# MB_RELAY.net
KiCad netlist of a schematic drawn in Altium Designer
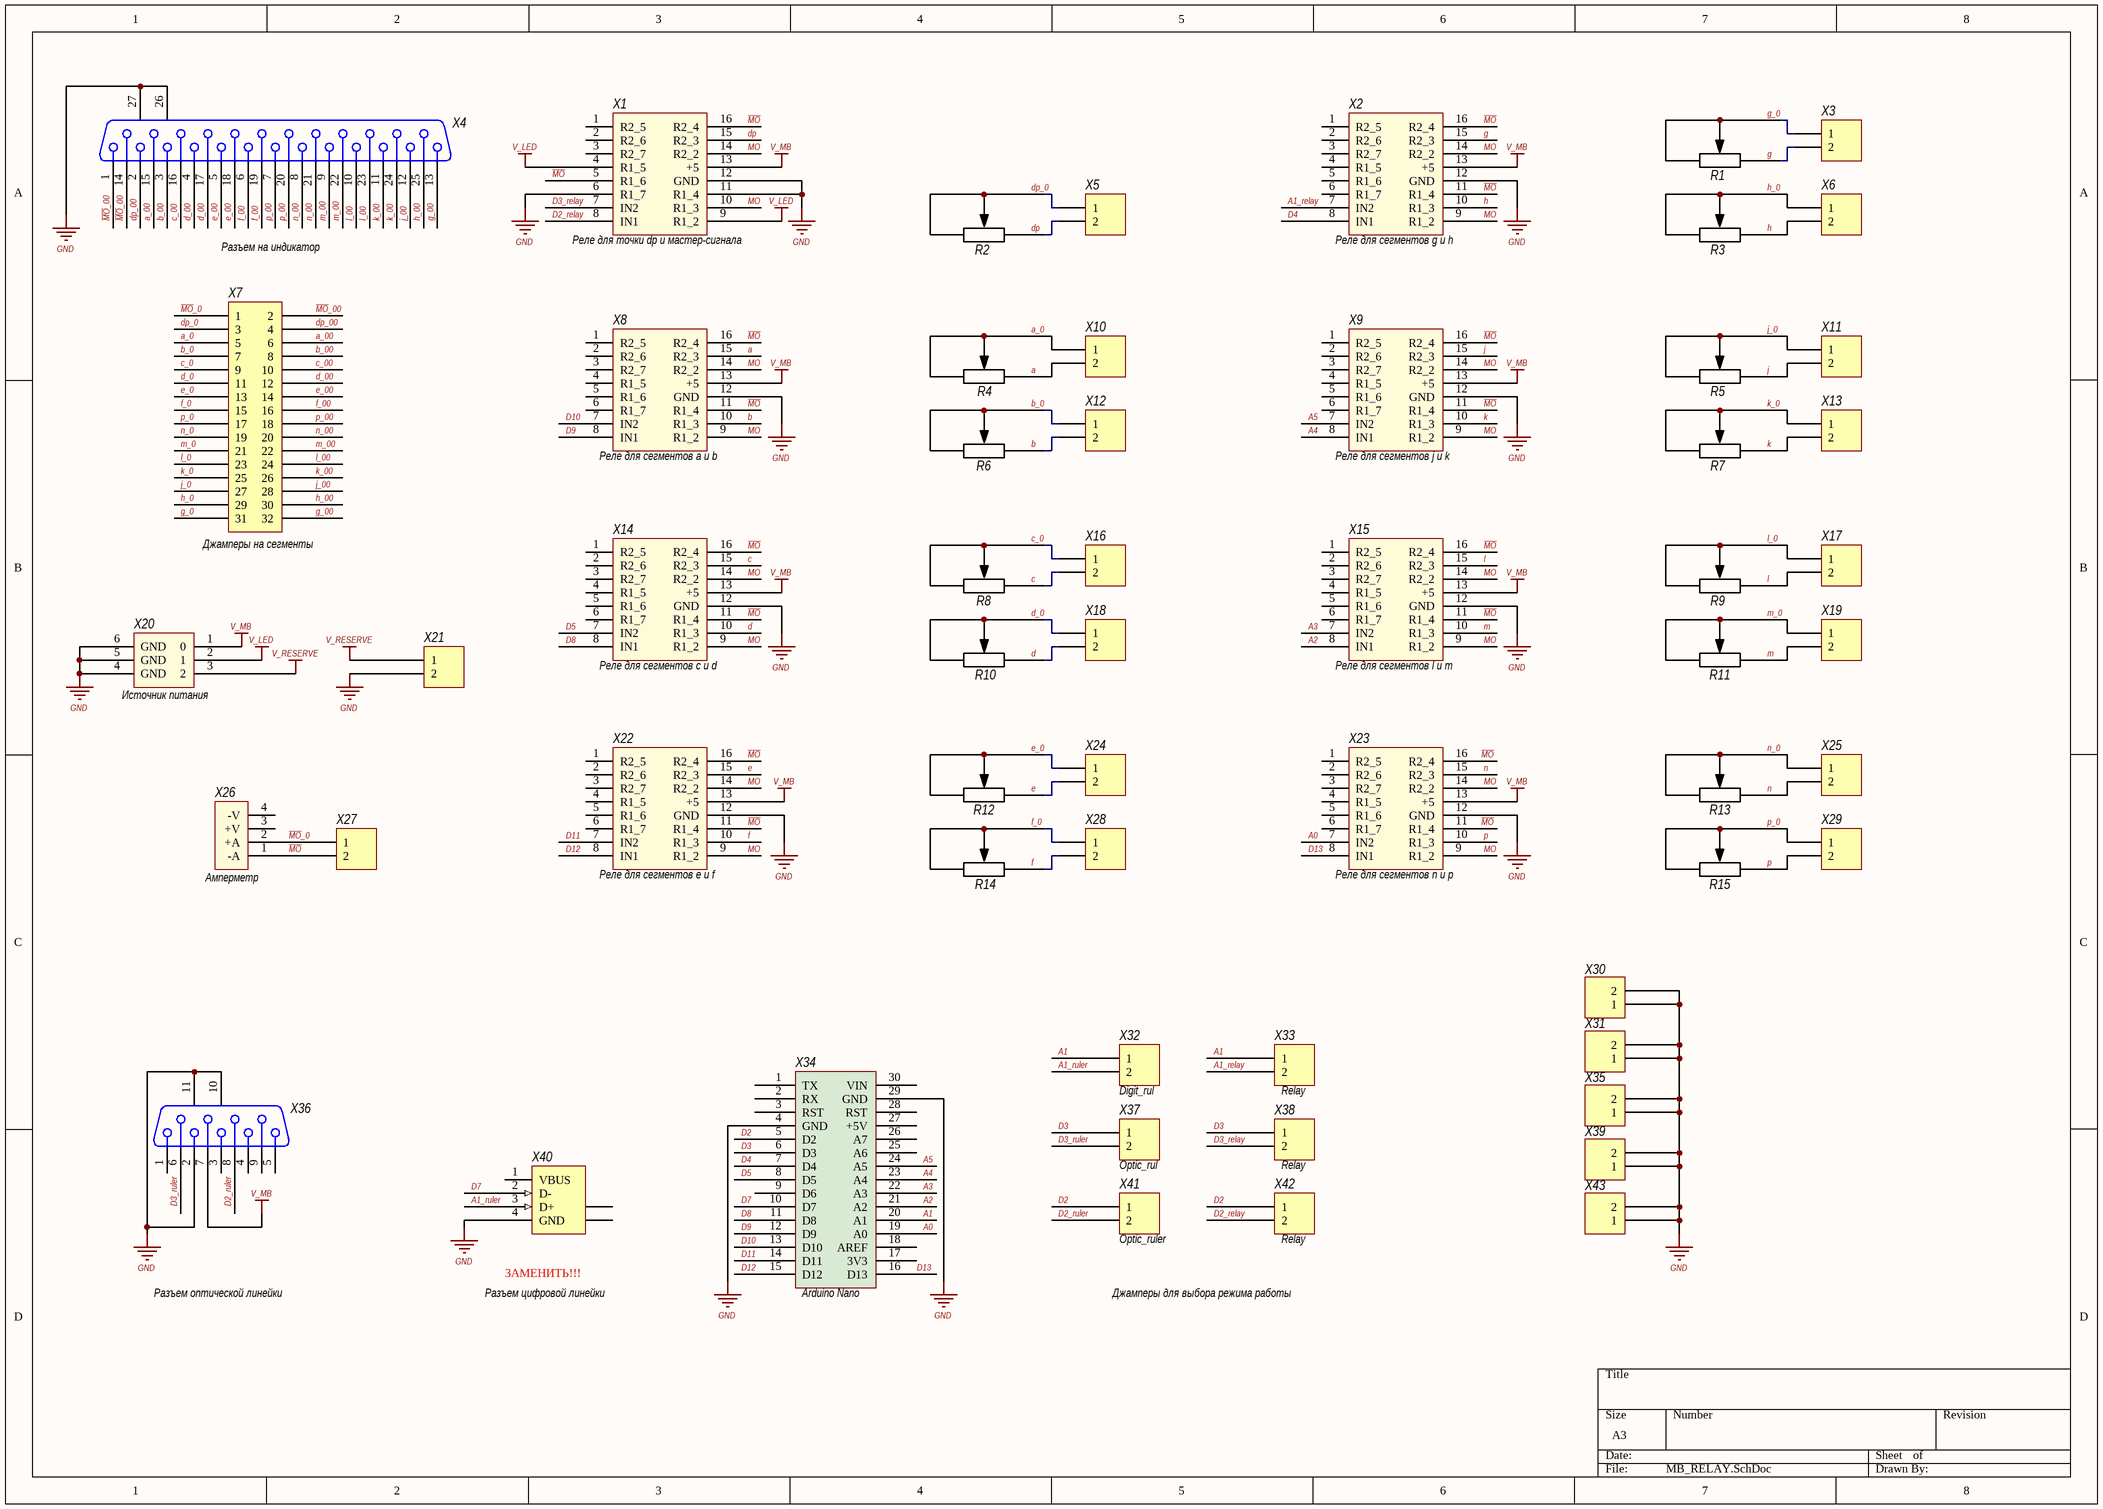
[diagram p0: MB_RELAY.SchDoc]

(export (version "E")
  (design (tool "Eeschema 10.0.6"))
  (components
    (comp (ref "R1")
      (value "RES 3266W")
      (footprint "aab_Passive:RES 3266W")
      (libsource (lib "aab_Schlib") (part "RES 3266W"))
    )
    (comp (ref "R2")
      (value "RES 3266W")
      (footprint "aab_Passive:RES 3266W")
      (libsource (lib "aab_Schlib") (part "RES 3266W"))
    )
    (comp (ref "R3")
      (value "RES 3266W")
      (footprint "aab_Passive:RES 3266W")
      (libsource (lib "aab_Schlib") (part "RES 3266W"))
    )
    (comp (ref "R4")
      (value "Переменнный резистор для")
      (footprint "aab_Passive:RES 3266W")
      (libsource (lib "aab_Schlib") (part "RES 3266W"))
    )
    (comp (ref "R5")
      (value "RES 3266W")
      (footprint "aab_Passive:RES 3266W")
      (libsource (lib "aab_Schlib") (part "RES 3266W"))
    )
    (comp (ref "R6")
      (value "RES 3266W")
      (footprint "aab_Passive:RES 3266W")
      (libsource (lib "aab_Schlib") (part "RES 3266W"))
    )
    (comp (ref "R7")
      (value "RES 3266W")
      (footprint "aab_Passive:RES 3266W")
      (libsource (lib "aab_Schlib") (part "RES 3266W"))
    )
    (comp (ref "R8")
      (value "RES 3266W")
      (footprint "aab_Passive:RES 3266W")
      (libsource (lib "aab_Schlib") (part "RES 3266W"))
    )
    (comp (ref "R9")
      (value "RES 3266W")
      (footprint "aab_Passive:RES 3266W")
      (libsource (lib "aab_Schlib") (part "RES 3266W"))
    )
    (comp (ref "R10")
      (value "RES 3266W")
      (footprint "aab_Passive:RES 3266W")
      (libsource (lib "aab_Schlib") (part "RES 3266W"))
    )
    (comp (ref "R11")
      (value "RES 3266W")
      (footprint "aab_Passive:RES 3266W")
      (libsource (lib "aab_Schlib") (part "RES 3266W"))
    )
    (comp (ref "R12")
      (value "RES 3266W")
      (footprint "aab_Passive:RES 3266W")
      (libsource (lib "aab_Schlib") (part "RES 3266W"))
    )
    (comp (ref "R13")
      (value "RES 3266W")
      (footprint "aab_Passive:RES 3266W")
      (libsource (lib "aab_Schlib") (part "RES 3266W"))
    )
    (comp (ref "R14")
      (value "RES 3266W")
      (footprint "aab_Passive:RES 3266W")
      (libsource (lib "aab_Schlib") (part "RES 3266W"))
    )
    (comp (ref "R15")
      (value "RES 3266W")
      (footprint "aab_Passive:RES 3266W")
      (libsource (lib "aab_Schlib") (part "RES 3266W"))
    )
    (comp (ref "X1")
      (value "Реле для точки dp и мастер-сигнала")
      (footprint "MEZ_RELAY")
      (libsource (lib "msp_SchLib") (part "MEZ_RELAY"))
    )
    (comp (ref "X2")
      (value "Реле для сегментов g и h")
      (footprint "MEZ_RELAY")
      (libsource (lib "msp_SchLib") (part "MEZ_RELAY"))
    )
    (comp (ref "X3")
      (value "GND")
      (footprint "HDR1X2")
      (description "Header, 2-Pin")
      (fields (field (name "PUBLISHER") "Altium Limited"))
      (libsource (lib "Miscellaneous Connectors") (part "Header 2"))
    )
    (comp (ref "X4")
      (value "D Connector 25")
      (footprint "DSUB1.385-2H25A")
      (description "Receptacle Assembly, 25 Position, Right Angle")
      (fields (field (name "PUBLISHER") "Altium Limited"))
      (libsource (lib "Miscellaneous Connectors") (part "D Connector 25"))
    )
    (comp (ref "X5")
      (value "GND")
      (footprint "HDR1X2")
      (description "Header, 2-Pin")
      (fields (field (name "PUBLISHER") "Altium Limited"))
      (libsource (lib "Miscellaneous Connectors") (part "Header 2"))
    )
    (comp (ref "X6")
      (value "GND")
      (footprint "HDR1X2")
      (description "Header, 2-Pin")
      (fields (field (name "PUBLISHER") "Altium Limited"))
      (libsource (lib "Miscellaneous Connectors") (part "Header 2"))
    )
    (comp (ref "X7")
      (value "Header 16X2")
      (footprint "HDR2X16")
      (description "Header, 16-Pin, Dual row")
      (fields (field (name "PUBLISHER") "Altium Limited"))
      (libsource (lib "Miscellaneous Connectors") (part "Header 16X2"))
    )
    (comp (ref "X8")
      (value "Реле для сегментов a и b")
      (footprint "MEZ_RELAY")
      (libsource (lib "msp_SchLib") (part "MEZ_RELAY"))
    )
    (comp (ref "X9")
      (value "Реле для сегментов j и k")
      (footprint "MEZ_RELAY")
      (libsource (lib "msp_SchLib") (part "MEZ_RELAY"))
    )
    (comp (ref "X10")
      (value "Header 2")
      (footprint "HDR1X2")
      (description "Header, 2-Pin")
      (fields (field (name "PUBLISHER") "Altium Limited"))
      (libsource (lib "Miscellaneous Connectors") (part "Header 2"))
    )
    (comp (ref "X11")
      (value "Header 2")
      (footprint "HDR1X2")
      (description "Header, 2-Pin")
      (fields (field (name "PUBLISHER") "Altium Limited"))
      (libsource (lib "Miscellaneous Connectors") (part "Header 2"))
    )
    (comp (ref "X12")
      (value "Header 2")
      (footprint "HDR1X2")
      (description "Header, 2-Pin")
      (fields (field (name "PUBLISHER") "Altium Limited"))
      (libsource (lib "Miscellaneous Connectors") (part "Header 2"))
    )
    (comp (ref "X13")
      (value "Header 2")
      (footprint "HDR1X2")
      (description "Header, 2-Pin")
      (fields (field (name "PUBLISHER") "Altium Limited"))
      (libsource (lib "Miscellaneous Connectors") (part "Header 2"))
    )
    (comp (ref "X14")
      (value "Реле для сегментов c и d")
      (footprint "MEZ_RELAY")
      (libsource (lib "msp_SchLib") (part "MEZ_RELAY"))
    )
    (comp (ref "X15")
      (value "Реле для сегментов l и m")
      (footprint "MEZ_RELAY")
      (libsource (lib "msp_SchLib") (part "MEZ_RELAY"))
    )
    (comp (ref "X16")
      (value "Header 2")
      (footprint "HDR1X2")
      (description "Header, 2-Pin")
      (fields (field (name "PUBLISHER") "Altium Limited"))
      (libsource (lib "Miscellaneous Connectors") (part "Header 2"))
    )
    (comp (ref "X17")
      (value "GND")
      (footprint "HDR1X2")
      (description "Header, 2-Pin")
      (fields (field (name "PUBLISHER") "Altium Limited"))
      (libsource (lib "Miscellaneous Connectors") (part "Header 2"))
    )
    (comp (ref "X18")
      (value "Header 2")
      (footprint "HDR1X2")
      (description "Header, 2-Pin")
      (fields (field (name "PUBLISHER") "Altium Limited"))
      (libsource (lib "Miscellaneous Connectors") (part "Header 2"))
    )
    (comp (ref "X19")
      (value "GND")
      (footprint "HDR1X2")
      (description "Header, 2-Pin")
      (fields (field (name "PUBLISHER") "Altium Limited"))
      (libsource (lib "Miscellaneous Connectors") (part "Header 2"))
    )
    (comp (ref "X20")
      (value "Источник питания")
      (footprint "vpl_Passive:POWER")
      (libsource (lib "msp_SchLib") (part "POWER"))
    )
    (comp (ref "X21")
      (value "Header 2")
      (footprint "HDR1X2")
      (description "Header, 2-Pin")
      (fields (field (name "PUBLISHER") "Altium Limited"))
      (libsource (lib "Miscellaneous Connectors") (part "Header 2"))
    )
    (comp (ref "X22")
      (value "Реле для сегментов e и f")
      (footprint "MEZ_RELAY")
      (libsource (lib "msp_SchLib") (part "MEZ_RELAY"))
    )
    (comp (ref "X23")
      (value "Реле для сегментов n и p")
      (footprint "MEZ_RELAY")
      (libsource (lib "msp_SchLib") (part "MEZ_RELAY"))
    )
    (comp (ref "X24")
      (value "GND")
      (footprint "HDR1X2")
      (description "Header, 2-Pin")
      (fields (field (name "PUBLISHER") "Altium Limited"))
      (libsource (lib "Miscellaneous Connectors") (part "Header 2"))
    )
    (comp (ref "X25")
      (value "GND")
      (footprint "HDR1X2")
      (description "Header, 2-Pin")
      (fields (field (name "PUBLISHER") "Altium Limited"))
      (libsource (lib "Miscellaneous Connectors") (part "Header 2"))
    )
    (comp (ref "X26")
      (value "Амперметр")
      (footprint "vpl_Passive:AMP_VOLTMETER")
      (libsource (lib "msp_SchLib") (part "AMP_VOLTMETR"))
    )
    (comp (ref "X27")
      (value "Header 2")
      (footprint "HDR1X2")
      (description "Header, 2-Pin")
      (fields (field (name "PUBLISHER") "Altium Limited"))
      (libsource (lib "Miscellaneous Connectors") (part "Header 2"))
    )
    (comp (ref "X28")
      (value "GND")
      (footprint "HDR1X2")
      (description "Header, 2-Pin")
      (fields (field (name "PUBLISHER") "Altium Limited"))
      (libsource (lib "Miscellaneous Connectors") (part "Header 2"))
    )
    (comp (ref "X29")
      (value "GND")
      (footprint "HDR1X2")
      (description "Header, 2-Pin")
      (fields (field (name "PUBLISHER") "Altium Limited"))
      (libsource (lib "Miscellaneous Connectors") (part "Header 2"))
    )
    (comp (ref "X30")
      (value "Header 2")
      (footprint "HDR1X2")
      (description "Header, 2-Pin")
      (fields (field (name "PUBLISHER") "Altium Limited"))
      (libsource (lib "") (part "Header 2_1"))
    )
    (comp (ref "X31")
      (value "GND")
      (footprint "HDR1X2")
      (description "Header, 2-Pin")
      (fields (field (name "PUBLISHER") "Altium Limited"))
      (libsource (lib "") (part "Header 2_1"))
    )
    (comp (ref "X32")
      (value "Digit_rul")
      (footprint "HDR1X2")
      (description "Header, 2-Pin")
      (fields (field (name "PUBLISHER") "Altium Limited"))
      (libsource (lib "Miscellaneous Connectors") (part "Header 2"))
    )
    (comp (ref "X33")
      (value "Relay")
      (footprint "HDR1X2")
      (description "Header, 2-Pin")
      (fields (field (name "PUBLISHER") "Altium Limited"))
      (libsource (lib "Miscellaneous Connectors") (part "Header 2"))
    )
    (comp (ref "X34")
      (value "Arduino Nano")
      (footprint "PCBComponent_1")
      (libsource (lib "Nano") (part "Component_1"))
    )
    (comp (ref "X35")
      (value "GND")
      (footprint "HDR1X2")
      (description "Header, 2-Pin")
      (fields (field (name "PUBLISHER") "Altium Limited"))
      (libsource (lib "") (part "Header 2_1"))
    )
    (comp (ref "X36")
      (value "D Connector 9")
      (footprint "DSUB1.385-2H9")
      (description "Receptacle Assembly, 9 Position, Right Angle")
      (fields (field (name "PUBLISHER") "Altium Limited"))
      (libsource (lib "Miscellaneous Connectors") (part "D Connector 9"))
    )
    (comp (ref "X37")
      (value "Optic_rul")
      (footprint "HDR1X2")
      (description "Header, 2-Pin")
      (fields (field (name "PUBLISHER") "Altium Limited"))
      (libsource (lib "Miscellaneous Connectors") (part "Header 2"))
    )
    (comp (ref "X38")
      (value "Relay")
      (footprint "HDR1X2")
      (description "Header, 2-Pin")
      (fields (field (name "PUBLISHER") "Altium Limited"))
      (libsource (lib "Miscellaneous Connectors") (part "Header 2"))
    )
    (comp (ref "X39")
      (value "GND")
      (footprint "HDR1X2")
      (description "Header, 2-Pin")
      (fields (field (name "PUBLISHER") "Altium Limited"))
      (libsource (lib "") (part "Header 2_1"))
    )
    (comp (ref "X40")
      (value "1-353576-1")
      (footprint "353576")
      (description "USB 1.1, Right Angle, SMT, A Type, Receptacle, 4 Position, White")
      (fields (field (name "PUBLISHER") "Altium Limited"))
      (libsource (lib "AMP Serial Bus USB") (part "1-353576-1"))
    )
    (comp (ref "X41")
      (value "Optic_ruler")
      (footprint "HDR1X2")
      (description "Header, 2-Pin")
      (fields (field (name "PUBLISHER") "Altium Limited"))
      (libsource (lib "Miscellaneous Connectors") (part "Header 2"))
    )
    (comp (ref "X42")
      (value "Relay")
      (footprint "HDR1X2")
      (description "Header, 2-Pin")
      (fields (field (name "PUBLISHER") "Altium Limited"))
      (libsource (lib "Miscellaneous Connectors") (part "Header 2"))
    )
    (comp (ref "X43")
      (value "GND")
      (footprint "HDR1X2")
      (description "Header, 2-Pin")
      (fields (field (name "PUBLISHER") "Altium Limited"))
      (libsource (lib "") (part "Header 2_1"))
    )
  )
  (nets
    (net (code "1") (name "/A0") (class "Default")
      (node (ref "X23") (pin "7") (pinfunction "IN2_7") (pintype "passive"))
      (node (ref "X34") (pin "19") (pinfunction "A0_19") (pintype "passive"))
    )
    (net (code "2") (name "/A1") (class "Default")
      (node (ref "X32") (pin "1") (pinfunction "1_1") (pintype "passive"))
      (node (ref "X33") (pin "1") (pinfunction "1_1") (pintype "passive"))
      (node (ref "X34") (pin "20") (pinfunction "A1_20") (pintype "passive"))
    )
    (net (code "3") (name "/A1_relay") (class "Default")
      (node (ref "X2") (pin "7") (pinfunction "IN2_7") (pintype "passive"))
      (node (ref "X33") (pin "2") (pinfunction "2_2") (pintype "passive"))
    )
    (net (code "4") (name "/A1_ruler") (class "Default")
      (node (ref "X32") (pin "2") (pinfunction "2_2") (pintype "passive"))
      (node (ref "X40") (pin "3") (pinfunction "D+_3") (pintype "input"))
    )
    (net (code "5") (name "/A2") (class "Default")
      (node (ref "X15") (pin "8") (pinfunction "IN1_8") (pintype "passive"))
      (node (ref "X34") (pin "21") (pinfunction "A2_21") (pintype "passive"))
    )
    (net (code "6") (name "/A3") (class "Default")
      (node (ref "X15") (pin "7") (pinfunction "IN2_7") (pintype "passive"))
      (node (ref "X34") (pin "22") (pinfunction "A3_22") (pintype "passive"))
    )
    (net (code "7") (name "/A4") (class "Default")
      (node (ref "X34") (pin "23") (pinfunction "A4_23") (pintype "passive"))
      (node (ref "X9") (pin "8") (pinfunction "IN1_8") (pintype "passive"))
    )
    (net (code "8") (name "/A5") (class "Default")
      (node (ref "X34") (pin "24") (pinfunction "A5_24") (pintype "passive"))
      (node (ref "X9") (pin "7") (pinfunction "IN2_7") (pintype "passive"))
    )
    (net (code "9") (name "/D2") (class "Default")
      (node (ref "X34") (pin "5") (pinfunction "D2_5") (pintype "passive"))
      (node (ref "X41") (pin "1") (pinfunction "1_1") (pintype "passive"))
      (node (ref "X42") (pin "1") (pinfunction "1_1") (pintype "passive"))
    )
    (net (code "10") (name "/D2_relay") (class "Default")
      (node (ref "X1") (pin "8") (pinfunction "IN1_8") (pintype "passive"))
      (node (ref "X42") (pin "2") (pinfunction "2_2") (pintype "passive"))
    )
    (net (code "11") (name "/D2_ruler") (class "Default")
      (node (ref "X36") (pin "8") (pinfunction "8_8") (pintype "passive"))
      (node (ref "X41") (pin "2") (pinfunction "2_2") (pintype "passive"))
    )
    (net (code "12") (name "/D3") (class "Default")
      (node (ref "X34") (pin "6") (pinfunction "D3_6") (pintype "passive"))
      (node (ref "X37") (pin "1") (pinfunction "1_1") (pintype "passive"))
      (node (ref "X38") (pin "1") (pinfunction "1_1") (pintype "passive"))
    )
    (net (code "13") (name "/D3_relay") (class "Default")
      (node (ref "X1") (pin "7") (pinfunction "IN2_7") (pintype "passive"))
      (node (ref "X38") (pin "2") (pinfunction "2_2") (pintype "passive"))
    )
    (net (code "14") (name "/D3_ruler") (class "Default")
      (node (ref "X36") (pin "6") (pinfunction "6_6") (pintype "passive"))
      (node (ref "X37") (pin "2") (pinfunction "2_2") (pintype "passive"))
    )
    (net (code "15") (name "/D4") (class "Default")
      (node (ref "X2") (pin "8") (pinfunction "IN1_8") (pintype "passive"))
      (node (ref "X34") (pin "7") (pinfunction "D4_7") (pintype "passive"))
    )
    (net (code "16") (name "/D5") (class "Default")
      (node (ref "X14") (pin "7") (pinfunction "IN2_7") (pintype "passive"))
      (node (ref "X34") (pin "8") (pinfunction "D5_8") (pintype "passive"))
    )
    (net (code "17") (name "/D7") (class "Default")
      (node (ref "X34") (pin "10") (pinfunction "D7_10") (pintype "passive"))
      (node (ref "X40") (pin "2") (pinfunction "D-_2") (pintype "input"))
    )
    (net (code "18") (name "/D8") (class "Default")
      (node (ref "X14") (pin "8") (pinfunction "IN1_8") (pintype "passive"))
      (node (ref "X34") (pin "11") (pinfunction "D8_11") (pintype "passive"))
    )
    (net (code "19") (name "/D9") (class "Default")
      (node (ref "X34") (pin "12") (pinfunction "D9_12") (pintype "passive"))
      (node (ref "X8") (pin "8") (pinfunction "IN1_8") (pintype "passive"))
    )
    (net (code "20") (name "/D10") (class "Default")
      (node (ref "X34") (pin "13") (pinfunction "D10_13") (pintype "passive"))
      (node (ref "X8") (pin "7") (pinfunction "IN2_7") (pintype "passive"))
    )
    (net (code "21") (name "/D11") (class "Default")
      (node (ref "X22") (pin "7") (pinfunction "IN2_7") (pintype "passive"))
      (node (ref "X34") (pin "14") (pinfunction "D11_14") (pintype "passive"))
    )
    (net (code "22") (name "/D12") (class "Default")
      (node (ref "X22") (pin "8") (pinfunction "IN1_8") (pintype "passive"))
      (node (ref "X34") (pin "15") (pinfunction "D12_15") (pintype "passive"))
    )
    (net (code "23") (name "/D13") (class "Default")
      (node (ref "X23") (pin "8") (pinfunction "IN1_8") (pintype "passive"))
      (node (ref "X34") (pin "16") (pinfunction "D13_16") (pintype "passive"))
    )
    (net (code "24") (name "/MO") (class "Default")
      (node (ref "X1") (pin "10") (pinfunction "R1_3_10") (pintype "passive"))
      (node (ref "X1") (pin "14") (pinfunction "R2_2_14") (pintype "passive"))
      (node (ref "X14") (pin "14") (pinfunction "R2_2_14") (pintype "passive"))
      (node (ref "X14") (pin "9") (pinfunction "R1_2_9") (pintype "passive"))
      (node (ref "X15") (pin "14") (pinfunction "R2_2_14") (pintype "passive"))
      (node (ref "X15") (pin "9") (pinfunction "R1_2_9") (pintype "passive"))
      (node (ref "X2") (pin "14") (pinfunction "R2_2_14") (pintype "passive"))
      (node (ref "X2") (pin "9") (pinfunction "R1_2_9") (pintype "passive"))
      (node (ref "X22") (pin "14") (pinfunction "R2_2_14") (pintype "passive"))
      (node (ref "X22") (pin "9") (pinfunction "R1_2_9") (pintype "passive"))
      (node (ref "X23") (pin "14") (pinfunction "R2_2_14") (pintype "passive"))
      (node (ref "X23") (pin "9") (pinfunction "R1_2_9") (pintype "passive"))
      (node (ref "X8") (pin "14") (pinfunction "R2_2_14") (pintype "passive"))
      (node (ref "X8") (pin "9") (pinfunction "R1_2_9") (pintype "passive"))
      (node (ref "X9") (pin "14") (pinfunction "R2_2_14") (pintype "passive"))
      (node (ref "X9") (pin "9") (pinfunction "R1_2_9") (pintype "passive"))
    )
    (net (code "25") (name "/a") (class "Default")
      (node (ref "R4") (pin "3") (pinfunction "3_3") (pintype "passive"))
      (node (ref "X10") (pin "2") (pinfunction "2_2") (pintype "passive"))
      (node (ref "X8") (pin "15") (pinfunction "R2_3_15") (pintype "passive"))
    )
    (net (code "26") (name "/a_0") (class "Default")
      (node (ref "R4") (pin "1") (pinfunction "1_1") (pintype "passive"))
      (node (ref "R4") (pin "2") (pinfunction "2_2") (pintype "passive"))
      (node (ref "X10") (pin "1") (pinfunction "1_1") (pintype "passive"))
      (node (ref "X7") (pin "5") (pinfunction "5_5") (pintype "passive"))
    )
    (net (code "27") (name "/a_00") (class "Default")
      (node (ref "X4") (pin "15") (pinfunction "15_15") (pintype "passive"))
      (node (ref "X7") (pin "6") (pinfunction "6_6") (pintype "passive"))
    )
    (net (code "28") (name "/b") (class "Default")
      (node (ref "R6") (pin "3") (pinfunction "3_3") (pintype "passive"))
      (node (ref "X12") (pin "2") (pinfunction "2_2") (pintype "passive"))
      (node (ref "X8") (pin "10") (pinfunction "R1_3_10") (pintype "passive"))
    )
    (net (code "29") (name "/b_0") (class "Default")
      (node (ref "R6") (pin "1") (pinfunction "1_1") (pintype "passive"))
      (node (ref "R6") (pin "2") (pinfunction "2_2") (pintype "passive"))
      (node (ref "X12") (pin "1") (pinfunction "1_1") (pintype "passive"))
      (node (ref "X7") (pin "7") (pinfunction "7_7") (pintype "passive"))
    )
    (net (code "30") (name "/b_00") (class "Default")
      (node (ref "X4") (pin "3") (pinfunction "3_3") (pintype "passive"))
      (node (ref "X7") (pin "8") (pinfunction "8_8") (pintype "passive"))
    )
    (net (code "31") (name "/c") (class "Default")
      (node (ref "R8") (pin "3") (pinfunction "3_3") (pintype "passive"))
      (node (ref "X14") (pin "15") (pinfunction "R2_3_15") (pintype "passive"))
      (node (ref "X16") (pin "2") (pinfunction "2_2") (pintype "passive"))
    )
    (net (code "32") (name "/c_0") (class "Default")
      (node (ref "R8") (pin "1") (pinfunction "1_1") (pintype "passive"))
      (node (ref "R8") (pin "2") (pinfunction "2_2") (pintype "passive"))
      (node (ref "X16") (pin "1") (pinfunction "1_1") (pintype "passive"))
      (node (ref "X7") (pin "9") (pinfunction "9_9") (pintype "passive"))
    )
    (net (code "33") (name "/c_00") (class "Default")
      (node (ref "X4") (pin "16") (pinfunction "16_16") (pintype "passive"))
      (node (ref "X7") (pin "10") (pinfunction "10_10") (pintype "passive"))
    )
    (net (code "34") (name "/d") (class "Default")
      (node (ref "R10") (pin "3") (pinfunction "3_3") (pintype "passive"))
      (node (ref "X14") (pin "10") (pinfunction "R1_3_10") (pintype "passive"))
      (node (ref "X18") (pin "2") (pinfunction "2_2") (pintype "passive"))
    )
    (net (code "35") (name "/d_00") (class "Default")
      (node (ref "X4") (pin "17") (pinfunction "17_17") (pintype "passive"))
      (node (ref "X4") (pin "4") (pinfunction "4_4") (pintype "passive"))
      (node (ref "X7") (pin "12") (pinfunction "12_12") (pintype "passive"))
    )
    (net (code "36") (name "/d_0") (class "Default")
      (node (ref "R10") (pin "1") (pinfunction "1_1") (pintype "passive"))
      (node (ref "R10") (pin "2") (pinfunction "2_2") (pintype "passive"))
      (node (ref "X18") (pin "1") (pinfunction "1_1") (pintype "passive"))
      (node (ref "X7") (pin "11") (pinfunction "11_11") (pintype "passive"))
    )
    (net (code "37") (name "/dp") (class "Default")
      (node (ref "R2") (pin "3") (pinfunction "3_3") (pintype "passive"))
      (node (ref "X1") (pin "15") (pinfunction "R2_3_15") (pintype "passive"))
      (node (ref "X5") (pin "2") (pinfunction "2_2") (pintype "passive"))
    )
    (net (code "38") (name "/dp_0") (class "Default")
      (node (ref "R2") (pin "1") (pinfunction "1_1") (pintype "passive"))
      (node (ref "R2") (pin "2") (pinfunction "2_2") (pintype "passive"))
      (node (ref "X5") (pin "1") (pinfunction "1_1") (pintype "passive"))
      (node (ref "X7") (pin "3") (pinfunction "3_3") (pintype "passive"))
    )
    (net (code "39") (name "/dp_00") (class "Default")
      (node (ref "X4") (pin "2") (pinfunction "2_2") (pintype "passive"))
      (node (ref "X7") (pin "4") (pinfunction "4_4") (pintype "passive"))
    )
    (net (code "40") (name "/e") (class "Default")
      (node (ref "R12") (pin "3") (pinfunction "3_3") (pintype "passive"))
      (node (ref "X22") (pin "15") (pinfunction "R2_3_15") (pintype "passive"))
      (node (ref "X24") (pin "2") (pinfunction "2_2") (pintype "passive"))
    )
    (net (code "41") (name "/e_00") (class "Default")
      (node (ref "X4") (pin "18") (pinfunction "18_18") (pintype "passive"))
      (node (ref "X4") (pin "5") (pinfunction "5_5") (pintype "passive"))
      (node (ref "X7") (pin "14") (pinfunction "14_14") (pintype "passive"))
    )
    (net (code "42") (name "/e_0") (class "Default")
      (node (ref "R12") (pin "1") (pinfunction "1_1") (pintype "passive"))
      (node (ref "R12") (pin "2") (pinfunction "2_2") (pintype "passive"))
      (node (ref "X24") (pin "1") (pinfunction "1_1") (pintype "passive"))
      (node (ref "X7") (pin "13") (pinfunction "13_13") (pintype "passive"))
    )
    (net (code "43") (name "/f") (class "Default")
      (node (ref "R14") (pin "3") (pinfunction "3_3") (pintype "passive"))
      (node (ref "X22") (pin "10") (pinfunction "R1_3_10") (pintype "passive"))
      (node (ref "X28") (pin "2") (pinfunction "2_2") (pintype "passive"))
    )
    (net (code "44") (name "/f_0") (class "Default")
      (node (ref "R14") (pin "1") (pinfunction "1_1") (pintype "passive"))
      (node (ref "R14") (pin "2") (pinfunction "2_2") (pintype "passive"))
      (node (ref "X28") (pin "1") (pinfunction "1_1") (pintype "passive"))
      (node (ref "X7") (pin "15") (pinfunction "15_15") (pintype "passive"))
    )
    (net (code "45") (name "/f_00") (class "Default")
      (node (ref "X4") (pin "19") (pinfunction "19_19") (pintype "passive"))
      (node (ref "X4") (pin "6") (pinfunction "6_6") (pintype "passive"))
      (node (ref "X7") (pin "16") (pinfunction "16_16") (pintype "passive"))
    )
    (net (code "46") (name "/g") (class "Default")
      (node (ref "R1") (pin "3") (pinfunction "3_3") (pintype "passive"))
      (node (ref "X2") (pin "15") (pinfunction "R2_3_15") (pintype "passive"))
      (node (ref "X3") (pin "2") (pinfunction "2_2") (pintype "passive"))
    )
    (net (code "47") (name "/g_00") (class "Default")
      (node (ref "X4") (pin "13") (pinfunction "13_13") (pintype "passive"))
      (node (ref "X7") (pin "32") (pinfunction "32_32") (pintype "passive"))
    )
    (net (code "48") (name "/g_0") (class "Default")
      (node (ref "R1") (pin "1") (pinfunction "1_1") (pintype "passive"))
      (node (ref "R1") (pin "2") (pinfunction "2_2") (pintype "passive"))
      (node (ref "X3") (pin "1") (pinfunction "1_1") (pintype "passive"))
      (node (ref "X7") (pin "31") (pinfunction "31_31") (pintype "passive"))
    )
    (net (code "49") (name "/h") (class "Default")
      (node (ref "R3") (pin "3") (pinfunction "3_3") (pintype "passive"))
      (node (ref "X2") (pin "10") (pinfunction "R1_3_10") (pintype "passive"))
      (node (ref "X6") (pin "2") (pinfunction "2_2") (pintype "passive"))
    )
    (net (code "50") (name "/h_0") (class "Default")
      (node (ref "R3") (pin "1") (pinfunction "1_1") (pintype "passive"))
      (node (ref "R3") (pin "2") (pinfunction "2_2") (pintype "passive"))
      (node (ref "X6") (pin "1") (pinfunction "1_1") (pintype "passive"))
      (node (ref "X7") (pin "29") (pinfunction "29_29") (pintype "passive"))
    )
    (net (code "51") (name "/h_00") (class "Default")
      (node (ref "X4") (pin "25") (pinfunction "25_25") (pintype "passive"))
      (node (ref "X7") (pin "30") (pinfunction "30_30") (pintype "passive"))
    )
    (net (code "52") (name "/j") (class "Default")
      (node (ref "R5") (pin "3") (pinfunction "3_3") (pintype "passive"))
      (node (ref "X11") (pin "2") (pinfunction "2_2") (pintype "passive"))
      (node (ref "X9") (pin "15") (pinfunction "R2_3_15") (pintype "passive"))
    )
    (net (code "53") (name "/j_00") (class "Default")
      (node (ref "X4") (pin "12") (pinfunction "12_12") (pintype "passive"))
      (node (ref "X7") (pin "28") (pinfunction "28_28") (pintype "passive"))
    )
    (net (code "54") (name "/j_0") (class "Default")
      (node (ref "R5") (pin "1") (pinfunction "1_1") (pintype "passive"))
      (node (ref "R5") (pin "2") (pinfunction "2_2") (pintype "passive"))
      (node (ref "X11") (pin "1") (pinfunction "1_1") (pintype "passive"))
      (node (ref "X7") (pin "27") (pinfunction "27_27") (pintype "passive"))
    )
    (net (code "55") (name "/k") (class "Default")
      (node (ref "R7") (pin "3") (pinfunction "3_3") (pintype "passive"))
      (node (ref "X13") (pin "2") (pinfunction "2_2") (pintype "passive"))
      (node (ref "X9") (pin "10") (pinfunction "R1_3_10") (pintype "passive"))
    )
    (net (code "56") (name "/k_00") (class "Default")
      (node (ref "X4") (pin "11") (pinfunction "11_11") (pintype "passive"))
      (node (ref "X4") (pin "24") (pinfunction "24_24") (pintype "passive"))
      (node (ref "X7") (pin "26") (pinfunction "26_26") (pintype "passive"))
    )
    (net (code "57") (name "/k_0") (class "Default")
      (node (ref "R7") (pin "1") (pinfunction "1_1") (pintype "passive"))
      (node (ref "R7") (pin "2") (pinfunction "2_2") (pintype "passive"))
      (node (ref "X13") (pin "1") (pinfunction "1_1") (pintype "passive"))
      (node (ref "X7") (pin "25") (pinfunction "25_25") (pintype "passive"))
    )
    (net (code "58") (name "/l") (class "Default")
      (node (ref "R9") (pin "3") (pinfunction "3_3") (pintype "passive"))
      (node (ref "X15") (pin "15") (pinfunction "R2_3_15") (pintype "passive"))
      (node (ref "X17") (pin "2") (pinfunction "2_2") (pintype "passive"))
    )
    (net (code "59") (name "/l_0") (class "Default")
      (node (ref "R9") (pin "1") (pinfunction "1_1") (pintype "passive"))
      (node (ref "R9") (pin "2") (pinfunction "2_2") (pintype "passive"))
      (node (ref "X17") (pin "1") (pinfunction "1_1") (pintype "passive"))
      (node (ref "X7") (pin "23") (pinfunction "23_23") (pintype "passive"))
    )
    (net (code "60") (name "/l_00") (class "Default")
      (node (ref "X4") (pin "10") (pinfunction "10_10") (pintype "passive"))
      (node (ref "X4") (pin "23") (pinfunction "23_23") (pintype "passive"))
      (node (ref "X7") (pin "24") (pinfunction "24_24") (pintype "passive"))
    )
    (net (code "61") (name "/m") (class "Default")
      (node (ref "R11") (pin "3") (pinfunction "3_3") (pintype "passive"))
      (node (ref "X15") (pin "10") (pinfunction "R1_3_10") (pintype "passive"))
      (node (ref "X19") (pin "2") (pinfunction "2_2") (pintype "passive"))
    )
    (net (code "62") (name "/m_0") (class "Default")
      (node (ref "R11") (pin "1") (pinfunction "1_1") (pintype "passive"))
      (node (ref "R11") (pin "2") (pinfunction "2_2") (pintype "passive"))
      (node (ref "X19") (pin "1") (pinfunction "1_1") (pintype "passive"))
      (node (ref "X7") (pin "21") (pinfunction "21_21") (pintype "passive"))
    )
    (net (code "63") (name "/m_00") (class "Default")
      (node (ref "X4") (pin "22") (pinfunction "22_22") (pintype "passive"))
      (node (ref "X4") (pin "9") (pinfunction "9_9") (pintype "passive"))
      (node (ref "X7") (pin "22") (pinfunction "22_22") (pintype "passive"))
    )
    (net (code "64") (name "/n") (class "Default")
      (node (ref "R13") (pin "3") (pinfunction "3_3") (pintype "passive"))
      (node (ref "X23") (pin "15") (pinfunction "R2_3_15") (pintype "passive"))
      (node (ref "X25") (pin "2") (pinfunction "2_2") (pintype "passive"))
    )
    (net (code "65") (name "/n_00") (class "Default")
      (node (ref "X4") (pin "21") (pinfunction "21_21") (pintype "passive"))
      (node (ref "X4") (pin "8") (pinfunction "8_8") (pintype "passive"))
      (node (ref "X7") (pin "20") (pinfunction "20_20") (pintype "passive"))
    )
    (net (code "66") (name "/n_0") (class "Default")
      (node (ref "R13") (pin "1") (pinfunction "1_1") (pintype "passive"))
      (node (ref "R13") (pin "2") (pinfunction "2_2") (pintype "passive"))
      (node (ref "X25") (pin "1") (pinfunction "1_1") (pintype "passive"))
      (node (ref "X7") (pin "19") (pinfunction "19_19") (pintype "passive"))
    )
    (net (code "67") (name "/p") (class "Default")
      (node (ref "R15") (pin "3") (pinfunction "3_3") (pintype "passive"))
      (node (ref "X23") (pin "10") (pinfunction "R1_3_10") (pintype "passive"))
      (node (ref "X29") (pin "2") (pinfunction "2_2") (pintype "passive"))
    )
    (net (code "68") (name "/p_0") (class "Default")
      (node (ref "R15") (pin "1") (pinfunction "1_1") (pintype "passive"))
      (node (ref "R15") (pin "2") (pinfunction "2_2") (pintype "passive"))
      (node (ref "X29") (pin "1") (pinfunction "1_1") (pintype "passive"))
      (node (ref "X7") (pin "17") (pinfunction "17_17") (pintype "passive"))
    )
    (net (code "69") (name "/p_00") (class "Default")
      (node (ref "X4") (pin "20") (pinfunction "20_20") (pintype "passive"))
      (node (ref "X4") (pin "7") (pinfunction "7_7") (pintype "passive"))
      (node (ref "X7") (pin "18") (pinfunction "18_18") (pintype "passive"))
    )
    (net (code "70") (name "/~{MO}") (class "Default")
      (node (ref "X1") (pin "16") (pinfunction "R2_4_16") (pintype "passive"))
      (node (ref "X1") (pin "5") (pinfunction "R1_6_5") (pintype "passive"))
      (node (ref "X14") (pin "11") (pinfunction "R1_4_11") (pintype "passive"))
      (node (ref "X14") (pin "16") (pinfunction "R2_4_16") (pintype "passive"))
      (node (ref "X15") (pin "11") (pinfunction "R1_4_11") (pintype "passive"))
      (node (ref "X15") (pin "16") (pinfunction "R2_4_16") (pintype "passive"))
      (node (ref "X2") (pin "11") (pinfunction "R1_4_11") (pintype "passive"))
      (node (ref "X2") (pin "16") (pinfunction "R2_4_16") (pintype "passive"))
      (node (ref "X22") (pin "11") (pinfunction "R1_4_11") (pintype "passive"))
      (node (ref "X22") (pin "16") (pinfunction "R2_4_16") (pintype "passive"))
      (node (ref "X23") (pin "11") (pinfunction "R1_4_11") (pintype "passive"))
      (node (ref "X23") (pin "16") (pinfunction "R2_4_16") (pintype "passive"))
      (node (ref "X26") (pin "1") (pinfunction "-A_1") (pintype "passive"))
      (node (ref "X27") (pin "2") (pinfunction "2_2") (pintype "passive"))
      (node (ref "X8") (pin "11") (pinfunction "R1_4_11") (pintype "passive"))
      (node (ref "X8") (pin "16") (pinfunction "R2_4_16") (pintype "passive"))
      (node (ref "X9") (pin "11") (pinfunction "R1_4_11") (pintype "passive"))
      (node (ref "X9") (pin "16") (pinfunction "R2_4_16") (pintype "passive"))
    )
    (net (code "71") (name "/~{MO}_0") (class "Default")
      (node (ref "X26") (pin "2") (pinfunction "+A_2") (pintype "passive"))
      (node (ref "X27") (pin "1") (pinfunction "1_1") (pintype "passive"))
      (node (ref "X7") (pin "1") (pinfunction "1_1") (pintype "passive"))
    )
    (net (code "72") (name "/~{MO}_00") (class "Default")
      (node (ref "X4") (pin "1") (pinfunction "1_1") (pintype "passive"))
      (node (ref "X4") (pin "14") (pinfunction "14_14") (pintype "passive"))
      (node (ref "X7") (pin "2") (pinfunction "2_2") (pintype "passive"))
    )
    (net (code "73") (name "GND") (class "Default")
      (node (ref "X1") (pin "11") (pinfunction "R1_4_11") (pintype "passive"))
      (node (ref "X1") (pin "12") (pinfunction "GND_12") (pintype "passive"))
      (node (ref "X1") (pin "6") (pinfunction "R1_7_6") (pintype "passive"))
      (node (ref "X14") (pin "12") (pinfunction "GND_12") (pintype "passive"))
      (node (ref "X15") (pin "12") (pinfunction "GND_12") (pintype "passive"))
      (node (ref "X2") (pin "12") (pinfunction "GND_12") (pintype "passive"))
      (node (ref "X20") (pin "4") (pinfunction "GND_4") (pintype "passive"))
      (node (ref "X20") (pin "5") (pinfunction "GND_5") (pintype "passive"))
      (node (ref "X20") (pin "6") (pinfunction "GND_6") (pintype "passive"))
      (node (ref "X21") (pin "2") (pinfunction "2_2") (pintype "passive"))
      (node (ref "X22") (pin "12") (pinfunction "GND_12") (pintype "passive"))
      (node (ref "X23") (pin "12") (pinfunction "GND_12") (pintype "passive"))
      (node (ref "X30") (pin "1") (pinfunction "1_1") (pintype "passive"))
      (node (ref "X30") (pin "2") (pinfunction "2_2") (pintype "passive"))
      (node (ref "X31") (pin "1") (pinfunction "1_1") (pintype "passive"))
      (node (ref "X31") (pin "2") (pinfunction "2_2") (pintype "passive"))
      (node (ref "X34") (pin "29") (pinfunction "GND_29") (pintype "passive"))
      (node (ref "X34") (pin "4") (pinfunction "GND_4") (pintype "passive"))
      (node (ref "X35") (pin "1") (pinfunction "1_1") (pintype "passive"))
      (node (ref "X35") (pin "2") (pinfunction "2_2") (pintype "passive"))
      (node (ref "X36") (pin "10") (pinfunction "MH1_10") (pintype "passive"))
      (node (ref "X36") (pin "11") (pinfunction "MH2_11") (pintype "passive"))
      (node (ref "X36") (pin "2") (pinfunction "2_2") (pintype "passive"))
      (node (ref "X39") (pin "1") (pinfunction "1_1") (pintype "passive"))
      (node (ref "X39") (pin "2") (pinfunction "2_2") (pintype "passive"))
      (node (ref "X4") (pin "26") (pinfunction "MH1_26") (pintype "passive"))
      (node (ref "X4") (pin "27") (pinfunction "MH2_27") (pintype "passive"))
      (node (ref "X40") (pin "4") (pinfunction "GND_4") (pintype "power_in"))
      (node (ref "X43") (pin "1") (pinfunction "1_1") (pintype "passive"))
      (node (ref "X43") (pin "2") (pinfunction "2_2") (pintype "passive"))
      (node (ref "X8") (pin "12") (pinfunction "GND_12") (pintype "passive"))
      (node (ref "X9") (pin "12") (pinfunction "GND_12") (pintype "passive"))
    )
    (net (code "74") (name "V_LED") (class "Default")
      (node (ref "X1") (pin "4") (pinfunction "R1_5_4") (pintype "passive"))
      (node (ref "X1") (pin "9") (pinfunction "R1_2_9") (pintype "passive"))
      (node (ref "X20") (pin "2") (pinfunction "1_2") (pintype "passive"))
    )
    (net (code "75") (name "V_MB") (class "Default")
      (node (ref "X1") (pin "13") (pinfunction "+5_13") (pintype "passive"))
      (node (ref "X14") (pin "13") (pinfunction "+5_13") (pintype "passive"))
      (node (ref "X15") (pin "13") (pinfunction "+5_13") (pintype "passive"))
      (node (ref "X2") (pin "13") (pinfunction "+5_13") (pintype "passive"))
      (node (ref "X20") (pin "1") (pinfunction "0_1") (pintype "passive"))
      (node (ref "X22") (pin "13") (pinfunction "+5_13") (pintype "passive"))
      (node (ref "X23") (pin "13") (pinfunction "+5_13") (pintype "passive"))
      (node (ref "X36") (pin "7") (pinfunction "7_7") (pintype "passive"))
      (node (ref "X8") (pin "13") (pinfunction "+5_13") (pintype "passive"))
      (node (ref "X9") (pin "13") (pinfunction "+5_13") (pintype "passive"))
    )
    (net (code "76") (name "V_RESERVE") (class "Default")
      (node (ref "X20") (pin "3") (pinfunction "2_3") (pintype "passive"))
      (node (ref "X21") (pin "1") (pinfunction "1_1") (pintype "passive"))
    )
    (net (code "77") (name "unconnected-(X1-R2_5-Pad1)") (class "Default")
      (node (ref "X1") (pin "1") (pinfunction "R2_5_1") (pintype "passive"))
    )
    (net (code "78") (name "unconnected-(X1-R2_6-Pad2)") (class "Default")
      (node (ref "X1") (pin "2") (pinfunction "R2_6_2") (pintype "passive"))
    )
    (net (code "79") (name "unconnected-(X1-R2_7-Pad3)") (class "Default")
      (node (ref "X1") (pin "3") (pinfunction "R2_7_3") (pintype "passive"))
    )
    (net (code "80") (name "unconnected-(X2-R1_5-Pad4)") (class "Default")
      (node (ref "X2") (pin "4") (pinfunction "R1_5_4") (pintype "passive"))
    )
    (net (code "81") (name "unconnected-(X2-R1_6-Pad5)") (class "Default")
      (node (ref "X2") (pin "5") (pinfunction "R1_6_5") (pintype "passive"))
    )
    (net (code "82") (name "unconnected-(X2-R1_7-Pad6)") (class "Default")
      (node (ref "X2") (pin "6") (pinfunction "R1_7_6") (pintype "passive"))
    )
    (net (code "83") (name "unconnected-(X2-R2_5-Pad1)") (class "Default")
      (node (ref "X2") (pin "1") (pinfunction "R2_5_1") (pintype "passive"))
    )
    (net (code "84") (name "unconnected-(X2-R2_6-Pad2)") (class "Default")
      (node (ref "X2") (pin "2") (pinfunction "R2_6_2") (pintype "passive"))
    )
    (net (code "85") (name "unconnected-(X2-R2_7-Pad3)") (class "Default")
      (node (ref "X2") (pin "3") (pinfunction "R2_7_3") (pintype "passive"))
    )
    (net (code "86") (name "unconnected-(X8-R1_5-Pad4)") (class "Default")
      (node (ref "X8") (pin "4") (pinfunction "R1_5_4") (pintype "passive"))
    )
    (net (code "87") (name "unconnected-(X8-R1_6-Pad5)") (class "Default")
      (node (ref "X8") (pin "5") (pinfunction "R1_6_5") (pintype "passive"))
    )
    (net (code "88") (name "unconnected-(X8-R1_7-Pad6)") (class "Default")
      (node (ref "X8") (pin "6") (pinfunction "R1_7_6") (pintype "passive"))
    )
    (net (code "89") (name "unconnected-(X8-R2_5-Pad1)") (class "Default")
      (node (ref "X8") (pin "1") (pinfunction "R2_5_1") (pintype "passive"))
    )
    (net (code "90") (name "unconnected-(X8-R2_6-Pad2)") (class "Default")
      (node (ref "X8") (pin "2") (pinfunction "R2_6_2") (pintype "passive"))
    )
    (net (code "91") (name "unconnected-(X8-R2_7-Pad3)") (class "Default")
      (node (ref "X8") (pin "3") (pinfunction "R2_7_3") (pintype "passive"))
    )
    (net (code "92") (name "unconnected-(X9-R1_5-Pad4)") (class "Default")
      (node (ref "X9") (pin "4") (pinfunction "R1_5_4") (pintype "passive"))
    )
    (net (code "93") (name "unconnected-(X9-R1_6-Pad5)") (class "Default")
      (node (ref "X9") (pin "5") (pinfunction "R1_6_5") (pintype "passive"))
    )
    (net (code "94") (name "unconnected-(X9-R1_7-Pad6)") (class "Default")
      (node (ref "X9") (pin "6") (pinfunction "R1_7_6") (pintype "passive"))
    )
    (net (code "95") (name "unconnected-(X9-R2_5-Pad1)") (class "Default")
      (node (ref "X9") (pin "1") (pinfunction "R2_5_1") (pintype "passive"))
    )
    (net (code "96") (name "unconnected-(X9-R2_6-Pad2)") (class "Default")
      (node (ref "X9") (pin "2") (pinfunction "R2_6_2") (pintype "passive"))
    )
    (net (code "97") (name "unconnected-(X9-R2_7-Pad3)") (class "Default")
      (node (ref "X9") (pin "3") (pinfunction "R2_7_3") (pintype "passive"))
    )
    (net (code "98") (name "unconnected-(X14-R1_5-Pad4)") (class "Default")
      (node (ref "X14") (pin "4") (pinfunction "R1_5_4") (pintype "passive"))
    )
    (net (code "99") (name "unconnected-(X14-R1_6-Pad5)") (class "Default")
      (node (ref "X14") (pin "5") (pinfunction "R1_6_5") (pintype "passive"))
    )
    (net (code "100") (name "unconnected-(X14-R1_7-Pad6)") (class "Default")
      (node (ref "X14") (pin "6") (pinfunction "R1_7_6") (pintype "passive"))
    )
    (net (code "101") (name "unconnected-(X14-R2_5-Pad1)") (class "Default")
      (node (ref "X14") (pin "1") (pinfunction "R2_5_1") (pintype "passive"))
    )
    (net (code "102") (name "unconnected-(X14-R2_6-Pad2)") (class "Default")
      (node (ref "X14") (pin "2") (pinfunction "R2_6_2") (pintype "passive"))
    )
    (net (code "103") (name "unconnected-(X14-R2_7-Pad3)") (class "Default")
      (node (ref "X14") (pin "3") (pinfunction "R2_7_3") (pintype "passive"))
    )
    (net (code "104") (name "unconnected-(X15-R1_5-Pad4)") (class "Default")
      (node (ref "X15") (pin "4") (pinfunction "R1_5_4") (pintype "passive"))
    )
    (net (code "105") (name "unconnected-(X15-R1_6-Pad5)") (class "Default")
      (node (ref "X15") (pin "5") (pinfunction "R1_6_5") (pintype "passive"))
    )
    (net (code "106") (name "unconnected-(X15-R1_7-Pad6)") (class "Default")
      (node (ref "X15") (pin "6") (pinfunction "R1_7_6") (pintype "passive"))
    )
    (net (code "107") (name "unconnected-(X15-R2_5-Pad1)") (class "Default")
      (node (ref "X15") (pin "1") (pinfunction "R2_5_1") (pintype "passive"))
    )
    (net (code "108") (name "unconnected-(X15-R2_6-Pad2)") (class "Default")
      (node (ref "X15") (pin "2") (pinfunction "R2_6_2") (pintype "passive"))
    )
    (net (code "109") (name "unconnected-(X15-R2_7-Pad3)") (class "Default")
      (node (ref "X15") (pin "3") (pinfunction "R2_7_3") (pintype "passive"))
    )
    (net (code "110") (name "unconnected-(X22-R1_5-Pad4)") (class "Default")
      (node (ref "X22") (pin "4") (pinfunction "R1_5_4") (pintype "passive"))
    )
    (net (code "111") (name "unconnected-(X22-R1_6-Pad5)") (class "Default")
      (node (ref "X22") (pin "5") (pinfunction "R1_6_5") (pintype "passive"))
    )
    (net (code "112") (name "unconnected-(X22-R1_7-Pad6)") (class "Default")
      (node (ref "X22") (pin "6") (pinfunction "R1_7_6") (pintype "passive"))
    )
    (net (code "113") (name "unconnected-(X22-R2_5-Pad1)") (class "Default")
      (node (ref "X22") (pin "1") (pinfunction "R2_5_1") (pintype "passive"))
    )
    (net (code "114") (name "unconnected-(X22-R2_6-Pad2)") (class "Default")
      (node (ref "X22") (pin "2") (pinfunction "R2_6_2") (pintype "passive"))
    )
    (net (code "115") (name "unconnected-(X22-R2_7-Pad3)") (class "Default")
      (node (ref "X22") (pin "3") (pinfunction "R2_7_3") (pintype "passive"))
    )
    (net (code "116") (name "unconnected-(X23-R1_5-Pad4)") (class "Default")
      (node (ref "X23") (pin "4") (pinfunction "R1_5_4") (pintype "passive"))
    )
    (net (code "117") (name "unconnected-(X23-R1_6-Pad5)") (class "Default")
      (node (ref "X23") (pin "5") (pinfunction "R1_6_5") (pintype "passive"))
    )
    (net (code "118") (name "unconnected-(X23-R1_7-Pad6)") (class "Default")
      (node (ref "X23") (pin "6") (pinfunction "R1_7_6") (pintype "passive"))
    )
    (net (code "119") (name "unconnected-(X23-R2_5-Pad1)") (class "Default")
      (node (ref "X23") (pin "1") (pinfunction "R2_5_1") (pintype "passive"))
    )
    (net (code "120") (name "unconnected-(X23-R2_6-Pad2)") (class "Default")
      (node (ref "X23") (pin "2") (pinfunction "R2_6_2") (pintype "passive"))
    )
    (net (code "121") (name "unconnected-(X23-R2_7-Pad3)") (class "Default")
      (node (ref "X23") (pin "3") (pinfunction "R2_7_3") (pintype "passive"))
    )
    (net (code "122") (name "unconnected-(X26-+V-Pad3)") (class "Default")
      (node (ref "X26") (pin "3") (pinfunction "+V_3") (pintype "passive"))
    )
    (net (code "123") (name "unconnected-(X26--V-Pad4)") (class "Default")
      (node (ref "X26") (pin "4") (pinfunction "-V_4") (pintype "passive"))
    )
    (net (code "124") (name "unconnected-(X34-+5V-Pad27)") (class "Default")
      (node (ref "X34") (pin "27") (pinfunction "+5V_27") (pintype "passive"))
    )
    (net (code "125") (name "unconnected-(X34-3V3-Pad17)") (class "Default")
      (node (ref "X34") (pin "17") (pinfunction "3V3_17") (pintype "passive"))
    )
    (net (code "126") (name "unconnected-(X34-A6-Pad25)") (class "Default")
      (node (ref "X34") (pin "25") (pinfunction "A6_25") (pintype "passive"))
    )
    (net (code "127") (name "unconnected-(X34-A7-Pad26)") (class "Default")
      (node (ref "X34") (pin "26") (pinfunction "A7_26") (pintype "passive"))
    )
    (net (code "128") (name "unconnected-(X34-AREF-Pad18)") (class "Default")
      (node (ref "X34") (pin "18") (pinfunction "AREF_18") (pintype "passive"))
    )
    (net (code "129") (name "unconnected-(X34-D6-Pad9)") (class "Default")
      (node (ref "X34") (pin "9") (pinfunction "D6_9") (pintype "passive"))
    )
    (net (code "130") (name "unconnected-(X34-RST-Pad3)") (class "Default")
      (node (ref "X34") (pin "3") (pinfunction "RST_3") (pintype "passive"))
    )
    (net (code "131") (name "unconnected-(X34-RST-Pad28)") (class "Default")
      (node (ref "X34") (pin "28") (pinfunction "RST_28") (pintype "passive"))
    )
    (net (code "132") (name "unconnected-(X34-RX-Pad2)") (class "Default")
      (node (ref "X34") (pin "2") (pinfunction "RX_2") (pintype "passive"))
    )
    (net (code "133") (name "unconnected-(X34-TX-Pad1)") (class "Default")
      (node (ref "X34") (pin "1") (pinfunction "TX_1") (pintype "passive"))
    )
    (net (code "134") (name "unconnected-(X34-VIN-Pad30)") (class "Default")
      (node (ref "X34") (pin "30") (pinfunction "VIN_30") (pintype "passive"))
    )
    (net (code "135") (name "unconnected-(X36-Pad1)") (class "Default")
      (node (ref "X36") (pin "1") (pinfunction "1_1") (pintype "passive"))
    )
    (net (code "136") (name "unconnected-(X36-Pad3)") (class "Default")
      (node (ref "X36") (pin "3") (pinfunction "3_3") (pintype "passive"))
    )
    (net (code "137") (name "unconnected-(X36-Pad4)") (class "Default")
      (node (ref "X36") (pin "4") (pinfunction "4_4") (pintype "passive"))
    )
    (net (code "138") (name "unconnected-(X36-Pad5)") (class "Default")
      (node (ref "X36") (pin "5") (pinfunction "5_5") (pintype "passive"))
    )
    (net (code "139") (name "unconnected-(X36-Pad9)") (class "Default")
      (node (ref "X36") (pin "9") (pinfunction "9_9") (pintype "passive"))
    )
    (net (code "140") (name "unconnected-(X40-SHLD-Pad5)") (class "Default")
      (node (ref "X40") (pin "5") (pinfunction "SHLD_5") (pintype "passive"))
    )
    (net (code "141") (name "unconnected-(X40-SHLD-Pad6)") (class "Default")
      (node (ref "X40") (pin "6") (pinfunction "SHLD_6") (pintype "passive"))
    )
    (net (code "142") (name "unconnected-(X40-VBUS-Pad1)") (class "Default")
      (node (ref "X40") (pin "1") (pinfunction "VBUS_1") (pintype "power_in"))
    )
  )
)
